# SAU-G0-EX_AHT-PL.net
KiCad netlist of a schematic drawn in Altium Designer
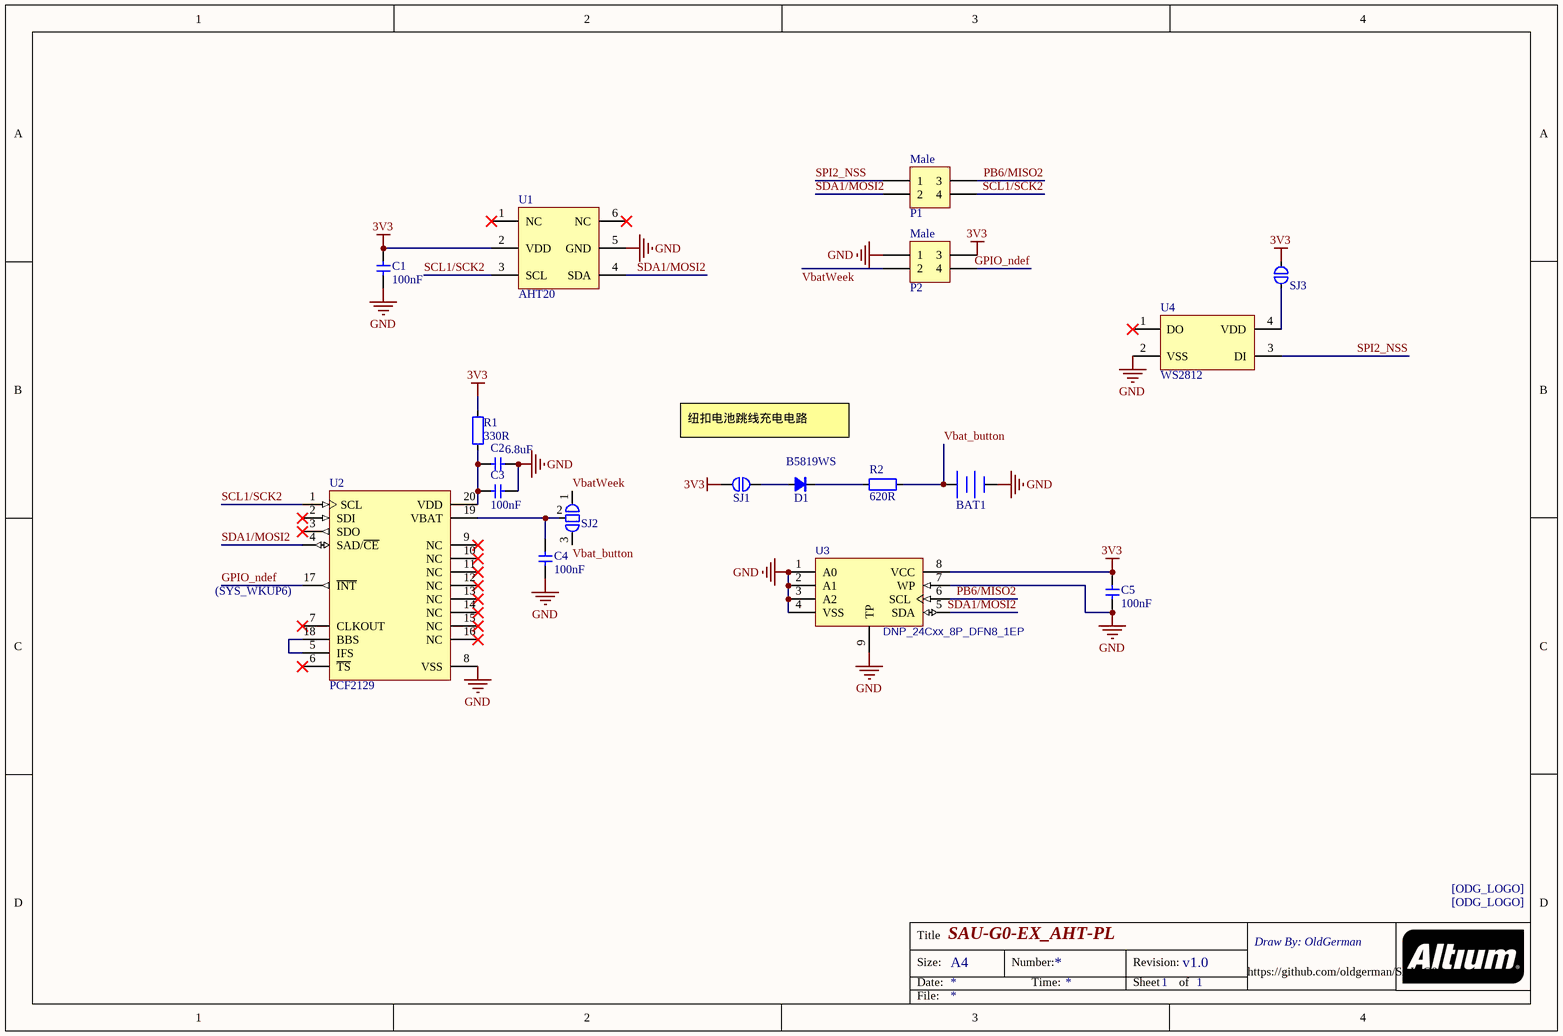
[diagram p0: SAU-G0-EX_AHT-PL.SchDoc]

(export (version "E")
  (design (tool "Eeschema 10.0.6"))
  (components
    (comp (ref "BAT1")
      (value "BAT")
      (footprint "MS621FE-FL11E")
      (description "锂电池")
      (libsource (lib "ODG_AD_Lib") (part "BAT"))
    )
    (comp (ref "C1")
      (value "100nF")
      (footprint "C0402")
      (description "Capacitor")
      (libsource (lib "ODG_AD_Lib") (part "CAP"))
    )
    (comp (ref "C2")
      (value "6.8uF")
      (footprint "C0402")
      (description "Capacitor")
      (libsource (lib "ODG_AD_Lib") (part "CAP"))
    )
    (comp (ref "C3")
      (value "100nF")
      (footprint "C0402")
      (description "Capacitor")
      (libsource (lib "ODG_AD_Lib") (part "CAP"))
    )
    (comp (ref "C4")
      (value "100nF")
      (footprint "C0402")
      (description "Capacitor")
      (libsource (lib "ODG_AD_Lib") (part "CAP"))
    )
    (comp (ref "C5")
      (value "100nF")
      (footprint "C0402")
      (description "Capacitor")
      (libsource (lib "ODG_AD_Lib") (part "CAP"))
    )
    (comp (ref "D1")
      (value "B5819WS")
      (footprint "SOD-323")
      (description "二极管")
      (libsource (lib "ODG_AD_Lib") (part "DIODE"))
    )
    (comp (ref "ODG1")
      (value "ODG_LOGO")
      (footprint "ODG_LOGO_soldermask")
      (libsource (lib "ODG_AD_Lib") (part "ODG_LOGO"))
    )
    (comp (ref "ODG2")
      (value "ODG_LOGO")
      (footprint "ODG_LOGO_soldermask")
      (libsource (lib "ODG_AD_Lib") (part "ODG_LOGO"))
    )
    (comp (ref "P1")
      (value "Male")
      (footprint "2.0mm_Male_2x2")
      (libsource (lib "ODG_AD_Lib") (part "CONN_2X2"))
    )
    (comp (ref "P2")
      (value "Male")
      (footprint "2.0mm_Male_2x2")
      (libsource (lib "ODG_AD_Lib") (part "CONN_2X2"))
    )
    (comp (ref "R1")
      (value "330R")
      (footprint "R0402")
      (description "Resistor")
      (libsource (lib "") (part "RES_1"))
    )
    (comp (ref "R2")
      (value "620R")
      (footprint "R0603")
      (description "Resistor")
      (libsource (lib "ODG_AD_Lib") (part "RES"))
    )
    (comp (ref "SJ1")
      (value "SJ_2P")
      (footprint "SJ_2P_MINI")
      (description "焊接跳线")
      (libsource (lib "") (part "SJ_2P_1"))
    )
    (comp (ref "SJ2")
      (value "SJ_3P")
      (footprint "SJ_3P_MINI")
      (description "焊接跳线二选一")
      (libsource (lib "ODG_AD_Lib") (part "SJ_3P"))
    )
    (comp (ref "SJ3")
      (value "SJ_2P")
      (footprint "SJ_2P_MINI")
      (description "焊接跳线")
      (libsource (lib "ODG_AD_Lib") (part "SJ_2P"))
    )
    (comp (ref "U1")
      (value "AHT20")
      (footprint "AHT20")
      (description "线性稳压芯片")
      (fields (field (name "版权归属") "源创客"))
      (libsource (lib "ODG_AD_Lib") (part "AHT20"))
    )
    (comp (ref "U2")
      (value "PCF2129")
      (footprint "NXP_SO20")
      (description "RTC")
      (libsource (lib "ODG_AD_Lib") (part "PCF2129"))
    )
    (comp (ref "U3")
      (value "DNP_24Cxx_8P_DFN8_1EP")
      (footprint "DFN-8-1EP_3x2mm_P0.5mm_EP1.75x1.45mm")
      (libsource (lib "ODG_AD_Lib") (part "24Cxx_8P_DFN8_1EP"))
    )
    (comp (ref "U4")
      (value "WS2812")
      (footprint "WS2812_2020")
      (libsource (lib "ODG_AD_Lib") (part "WS2812"))
    )
  )
  (nets
    (net (code "1") (name "/GPIO_ndef") (class "Default")
      (node (ref "P2") (pin "4") (pinfunction "4_4") (pintype "passive"))
      (node (ref "U2") (pin "17") (pinfunction "~{INT}_17") (pintype "output"))
    )
    (net (code "2") (name "/PB6{slash}MISO2") (class "Default")
      (node (ref "P1") (pin "3") (pinfunction "3_3") (pintype "passive"))
      (node (ref "U3") (pin "6") (pinfunction "SCL_6") (pintype "input"))
    )
    (net (code "3") (name "/SCL1{slash}SCK2") (class "Default")
      (node (ref "P1") (pin "4") (pinfunction "4_4") (pintype "passive"))
      (node (ref "U1") (pin "3") (pinfunction "SCL_3") (pintype "passive"))
      (node (ref "U2") (pin "1") (pinfunction "SCL_1") (pintype "input"))
    )
    (net (code "4") (name "/SDA1{slash}MOSI2") (class "Default")
      (node (ref "P1") (pin "2") (pinfunction "2_2") (pintype "passive"))
      (node (ref "U1") (pin "4") (pinfunction "SDA_4") (pintype "passive"))
      (node (ref "U2") (pin "4") (pinfunction "SAD/~{CE}_4") (pintype "bidirectional"))
      (node (ref "U3") (pin "5") (pinfunction "SDA_5") (pintype "bidirectional"))
    )
    (net (code "5") (name "/SPI2_NSS") (class "Default")
      (node (ref "P1") (pin "1") (pinfunction "1_1") (pintype "passive"))
      (node (ref "U4") (pin "3") (pinfunction "DI_3") (pintype "passive"))
    )
    (net (code "6") (name "/VbatWeek") (class "Default")
      (node (ref "P2") (pin "2") (pinfunction "2_2") (pintype "passive"))
      (node (ref "SJ2") (pin "1") (pinfunction "1_1") (pintype "passive"))
    )
    (net (code "7") (name "/Vbat_button") (class "Default")
      (node (ref "BAT1") (pin "1") (pinfunction "+_1") (pintype "passive"))
      (node (ref "R2") (pin "2") (pinfunction "2_2") (pintype "passive"))
      (node (ref "SJ2") (pin "3") (pinfunction "3_3") (pintype "passive"))
    )
    (net (code "8") (name "3V3") (class "Default")
      (node (ref "C1") (pin "1") (pinfunction "1_1") (pintype "passive"))
      (node (ref "C5") (pin "1") (pinfunction "1_1") (pintype "passive"))
      (node (ref "P2") (pin "3") (pinfunction "3_3") (pintype "passive"))
      (node (ref "R1") (pin "2") (pinfunction "2_2") (pintype "passive"))
      (node (ref "SJ1") (pin "2") (pinfunction "2_2") (pintype "passive"))
      (node (ref "SJ3") (pin "1") (pinfunction "1_1") (pintype "passive"))
      (node (ref "U1") (pin "2") (pinfunction "VDD_2") (pintype "passive"))
      (node (ref "U3") (pin "8") (pinfunction "VCC_8") (pintype "passive"))
    )
    (net (code "9") (name "GND") (class "Default")
      (node (ref "BAT1") (pin "2") (pinfunction "-_2") (pintype "passive"))
      (node (ref "C1") (pin "2") (pinfunction "2_2") (pintype "passive"))
      (node (ref "C2") (pin "2") (pinfunction "2_2") (pintype "passive"))
      (node (ref "C3") (pin "2") (pinfunction "2_2") (pintype "passive"))
      (node (ref "C4") (pin "2") (pinfunction "2_2") (pintype "passive"))
      (node (ref "C5") (pin "2") (pinfunction "2_2") (pintype "passive"))
      (node (ref "P2") (pin "1") (pinfunction "1_1") (pintype "passive"))
      (node (ref "U1") (pin "5") (pinfunction "GND_5") (pintype "passive"))
      (node (ref "U2") (pin "8") (pinfunction "VSS_8") (pintype "power_in"))
      (node (ref "U3") (pin "1") (pinfunction "A0_1") (pintype "passive"))
      (node (ref "U3") (pin "2") (pinfunction "A1_2") (pintype "passive"))
      (node (ref "U3") (pin "3") (pinfunction "A2_3") (pintype "passive"))
      (node (ref "U3") (pin "4") (pinfunction "VSS_4") (pintype "passive"))
      (node (ref "U3") (pin "7") (pinfunction "WP_7") (pintype "input"))
      (node (ref "U3") (pin "9") (pinfunction "TP_9") (pintype "passive"))
      (node (ref "U4") (pin "2") (pinfunction "VSS_2") (pintype "passive"))
    )
    (net (code "10") (name "Net-(D1-A)") (class "Default")
      (node (ref "D1") (pin "1") (pinfunction "A_1") (pintype "passive"))
      (node (ref "SJ1") (pin "1") (pinfunction "1_1") (pintype "passive"))
    )
    (net (code "11") (name "Net-(D1-C)") (class "Default")
      (node (ref "D1") (pin "2") (pinfunction "C_2") (pintype "passive"))
      (node (ref "R2") (pin "1") (pinfunction "1_1") (pintype "passive"))
    )
    (net (code "12") (name "Net-(U2-BBS)") (class "Default")
      (node (ref "U2") (pin "18") (pinfunction "BBS_18") (pintype "power_in"))
      (node (ref "U2") (pin "5") (pinfunction "IFS_5") (pintype "power_in"))
    )
    (net (code "13") (name "Net-(U2-VBAT)") (class "Default")
      (node (ref "C4") (pin "1") (pinfunction "1_1") (pintype "passive"))
      (node (ref "SJ2") (pin "2") (pinfunction "2_2") (pintype "passive"))
      (node (ref "U2") (pin "19") (pinfunction "VBAT_19") (pintype "power_in"))
    )
    (net (code "14") (name "Net-(U2-VDD)") (class "Default")
      (node (ref "C2") (pin "1") (pinfunction "1_1") (pintype "passive"))
      (node (ref "C3") (pin "1") (pinfunction "1_1") (pintype "passive"))
      (node (ref "R1") (pin "1") (pinfunction "1_1") (pintype "passive"))
      (node (ref "U2") (pin "20") (pinfunction "VDD_20") (pintype "power_in"))
    )
    (net (code "15") (name "Net-(U4-VDD)") (class "Default")
      (node (ref "SJ3") (pin "2") (pinfunction "2_2") (pintype "passive"))
      (node (ref "U4") (pin "4") (pinfunction "VDD_4") (pintype "passive"))
    )
    (net (code "16") (name "unconnected-(U1-NC-Pad1)") (class "Default")
      (node (ref "U1") (pin "1") (pinfunction "NC_1") (pintype "passive+no_connect"))
    )
    (net (code "17") (name "unconnected-(U1-NC-Pad6)") (class "Default")
      (node (ref "U1") (pin "6") (pinfunction "NC_6") (pintype "passive+no_connect"))
    )
    (net (code "18") (name "unconnected-(U2-CLKOUT-Pad7)") (class "Default")
      (node (ref "U2") (pin "7") (pinfunction "CLKOUT_7") (pintype "power_in+no_connect"))
    )
    (net (code "19") (name "unconnected-(U2-NC-Pad9)") (class "Default")
      (node (ref "U2") (pin "9") (pinfunction "NC_9") (pintype "power_in+no_connect"))
    )
    (net (code "20") (name "unconnected-(U2-NC-Pad10)") (class "Default")
      (node (ref "U2") (pin "10") (pinfunction "NC_10") (pintype "power_in+no_connect"))
    )
    (net (code "21") (name "unconnected-(U2-NC-Pad11)") (class "Default")
      (node (ref "U2") (pin "11") (pinfunction "NC_11") (pintype "power_in+no_connect"))
    )
    (net (code "22") (name "unconnected-(U2-NC-Pad12)") (class "Default")
      (node (ref "U2") (pin "12") (pinfunction "NC_12") (pintype "power_in+no_connect"))
    )
    (net (code "23") (name "unconnected-(U2-NC-Pad13)") (class "Default")
      (node (ref "U2") (pin "13") (pinfunction "NC_13") (pintype "power_in+no_connect"))
    )
    (net (code "24") (name "unconnected-(U2-NC-Pad14)") (class "Default")
      (node (ref "U2") (pin "14") (pinfunction "NC_14") (pintype "power_in+no_connect"))
    )
    (net (code "25") (name "unconnected-(U2-NC-Pad15)") (class "Default")
      (node (ref "U2") (pin "15") (pinfunction "NC_15") (pintype "power_in+no_connect"))
    )
    (net (code "26") (name "unconnected-(U2-NC-Pad16)") (class "Default")
      (node (ref "U2") (pin "16") (pinfunction "NC_16") (pintype "power_in+no_connect"))
    )
    (net (code "27") (name "unconnected-(U2-SDI-Pad2)") (class "Default")
      (node (ref "U2") (pin "2") (pinfunction "SDI_2") (pintype "input+no_connect"))
    )
    (net (code "28") (name "unconnected-(U2-SDO-Pad3)") (class "Default")
      (node (ref "U2") (pin "3") (pinfunction "SDO_3") (pintype "output+no_connect"))
    )
    (net (code "29") (name "unconnected-(U2-~{TS}-Pad6)") (class "Default")
      (node (ref "U2") (pin "6") (pinfunction "~{TS}_6") (pintype "power_in+no_connect"))
    )
    (net (code "30") (name "unconnected-(U4-DO-Pad1)") (class "Default")
      (node (ref "U4") (pin "1") (pinfunction "DO_1") (pintype "passive+no_connect"))
    )
  )
)
